# IP5389.net
KiCad netlist of a schematic drawn in Altium Designer
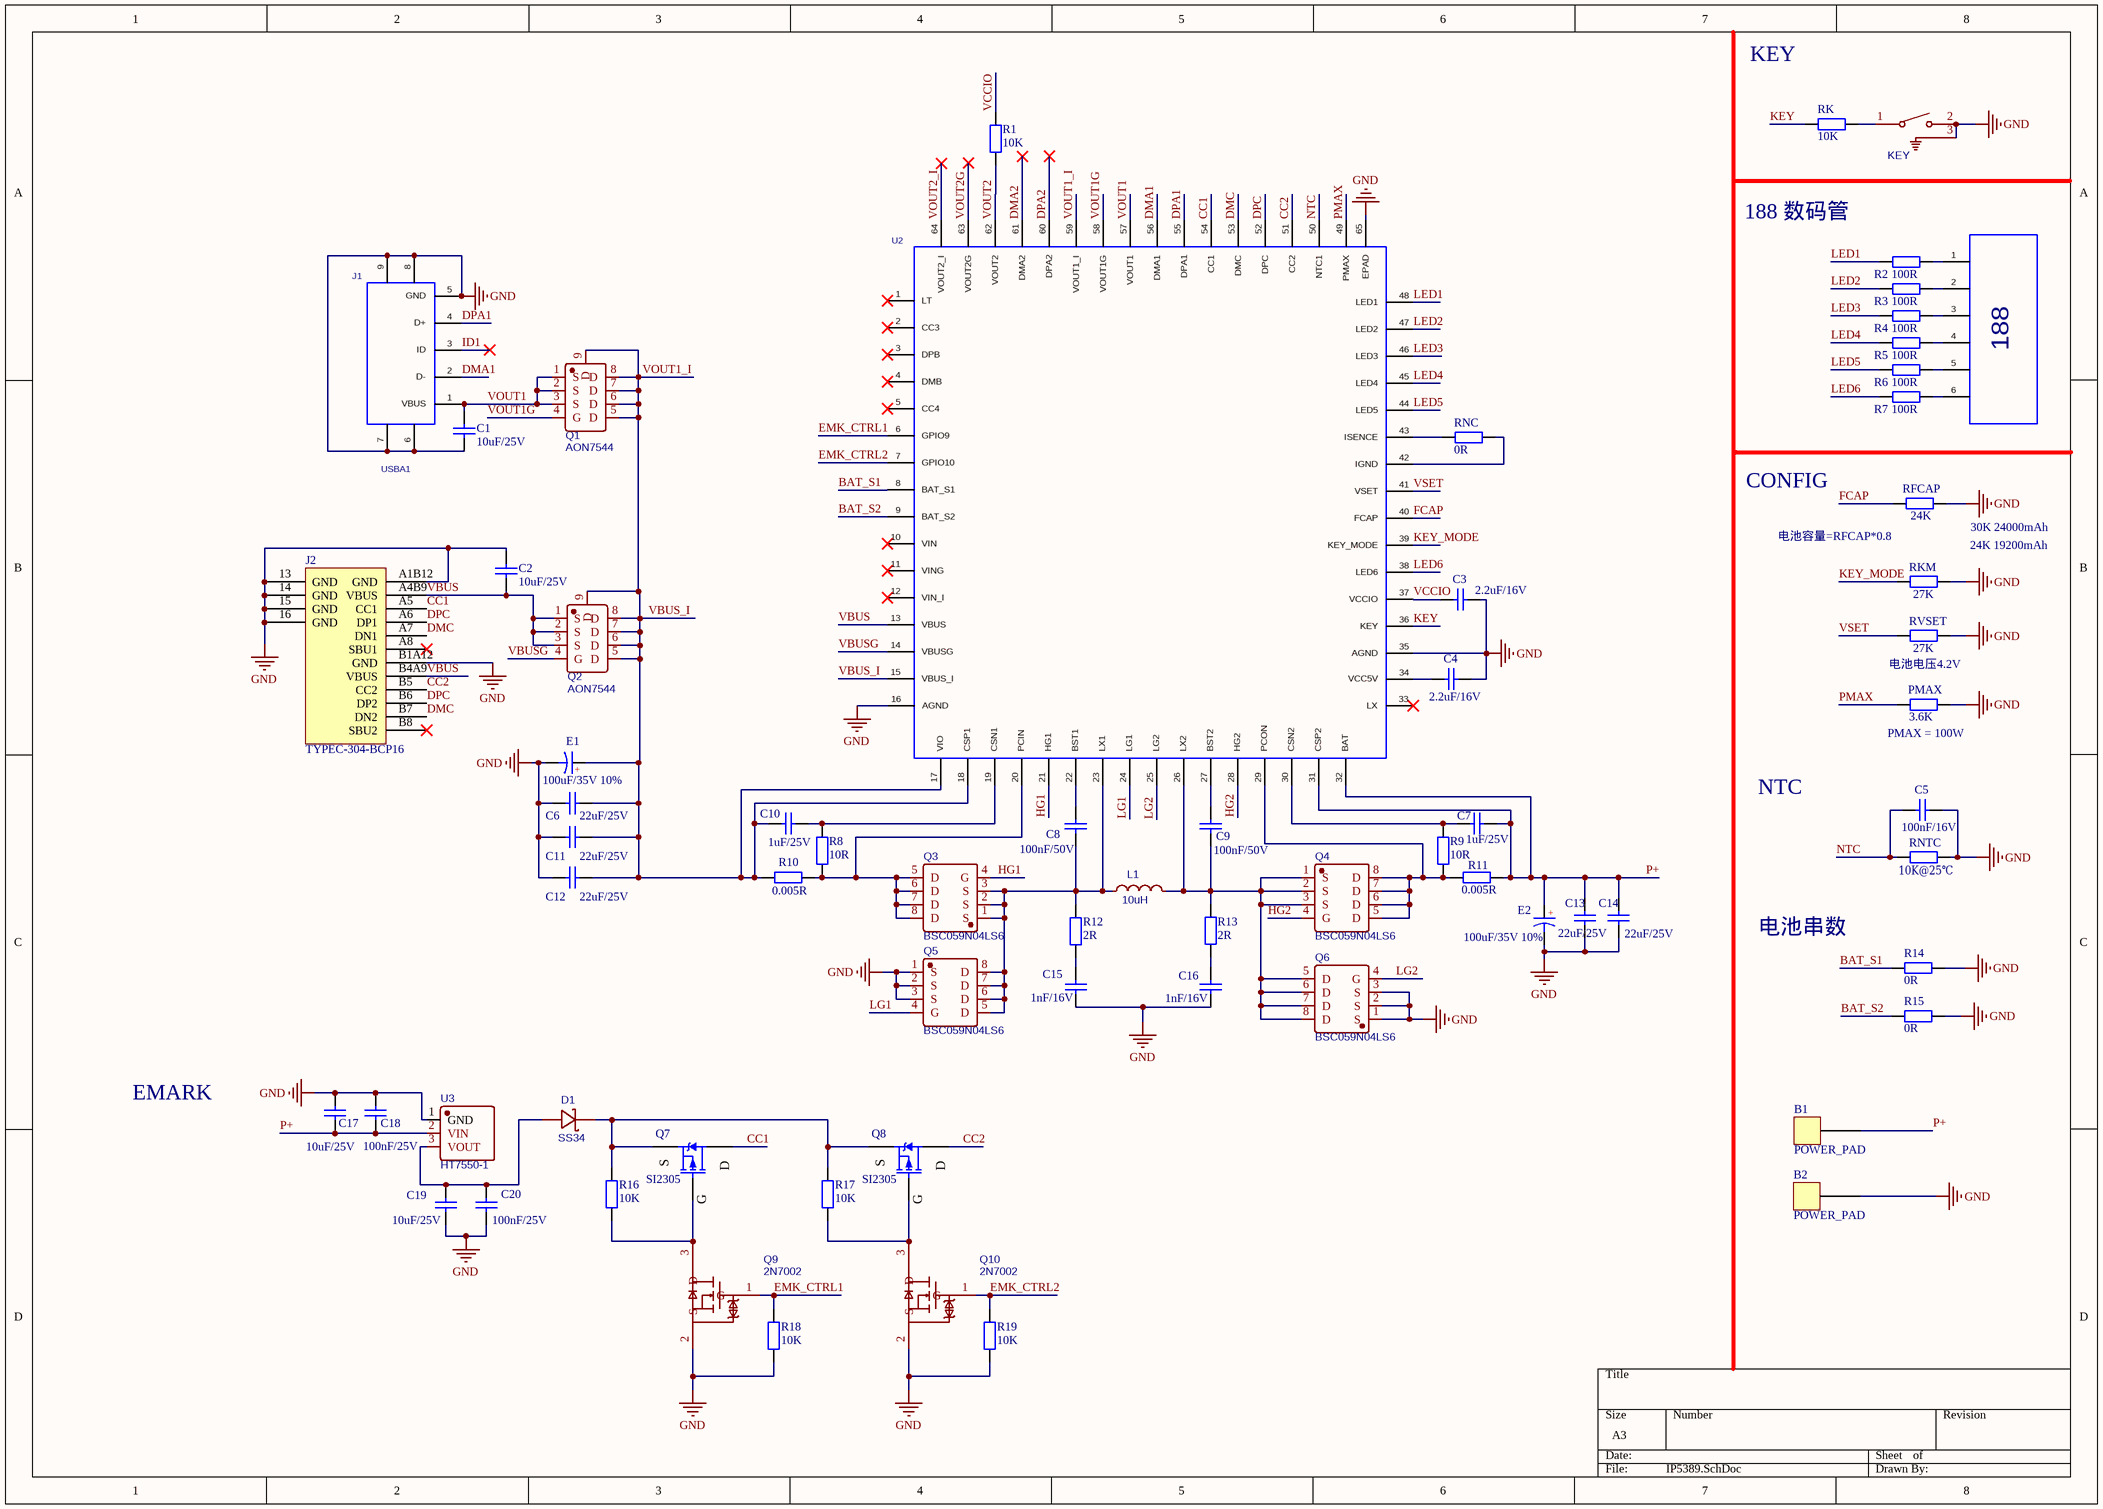
[diagram p0: IP5389.SchDoc]

(export (version "E")
  (design (tool "Eeschema 10.0.6"))
  (components
    (comp (ref "B1")
      (value "POWER_PAD")
      (footprint "POWER_PAD")
      (libsource (lib "IP5389_SCHLIB") (part "POWER_PAD"))
    )
    (comp (ref "B2")
      (value "POWER_PAD")
      (footprint "POWER_PAD")
      (libsource (lib "IP5389_SCHLIB") (part "POWER_PAD"))
    )
    (comp (ref "C1")
      (value "10uF/25V")
      (footprint "C0603_M")
      (description "贴片电容")
      (libsource (lib "0.1 - 电阻-电容-电感-晶振-晶体-磁珠-电位器") (part "C"))
    )
    (comp (ref "C2")
      (value "10uF/25V")
      (footprint "C0603_M")
      (description "贴片电容")
      (libsource (lib "0.1 - 电阻-电容-电感-晶振-晶体-磁珠-电位器") (part "C"))
    )
    (comp (ref "C3")
      (value "2.2uF/16V")
      (footprint "C0603_M")
      (description "贴片电容")
      (libsource (lib "0.1 - 电阻-电容-电感-晶振-晶体-磁珠-电位器") (part "C"))
    )
    (comp (ref "C4")
      (value "2.2uF/16V")
      (footprint "C0603_M")
      (description "贴片电容")
      (libsource (lib "0.1 - 电阻-电容-电感-晶振-晶体-磁珠-电位器") (part "C"))
    )
    (comp (ref "C5")
      (value "100nF/16V")
      (footprint "C0603_M")
      (description "贴片电容")
      (libsource (lib "0.1 - 电阻-电容-电感-晶振-晶体-磁珠-电位器") (part "C"))
    )
    (comp (ref "C6")
      (value "22uF/25V")
      (footprint "C0603_M")
      (description "贴片电容")
      (libsource (lib "0.1 - 电阻-电容-电感-晶振-晶体-磁珠-电位器") (part "C"))
    )
    (comp (ref "C7")
      (value "1uF/25V")
      (footprint "C0603_M")
      (description "贴片电容")
      (libsource (lib "0.1 - 电阻-电容-电感-晶振-晶体-磁珠-电位器") (part "C"))
    )
    (comp (ref "C8")
      (value "100nF/50V")
      (footprint "C0603_M")
      (description "贴片电容")
      (libsource (lib "0.1 - 电阻-电容-电感-晶振-晶体-磁珠-电位器") (part "C"))
    )
    (comp (ref "C9")
      (value "100nF/50V")
      (footprint "C0603_M")
      (description "贴片电容")
      (libsource (lib "0.1 - 电阻-电容-电感-晶振-晶体-磁珠-电位器") (part "C"))
    )
    (comp (ref "C10")
      (value "1uF/25V")
      (footprint "C0603_M")
      (description "贴片电容")
      (libsource (lib "0.1 - 电阻-电容-电感-晶振-晶体-磁珠-电位器") (part "C"))
    )
    (comp (ref "C11")
      (value "22uF/25V")
      (footprint "C0603_M")
      (description "贴片电容")
      (libsource (lib "0.1 - 电阻-电容-电感-晶振-晶体-磁珠-电位器") (part "C"))
    )
    (comp (ref "C12")
      (value "22uF/25V")
      (footprint "C0603_M")
      (description "贴片电容")
      (libsource (lib "0.1 - 电阻-电容-电感-晶振-晶体-磁珠-电位器") (part "C"))
    )
    (comp (ref "C13")
      (value "22uF/25V")
      (footprint "C0603_M")
      (description "贴片电容")
      (libsource (lib "0.1 - 电阻-电容-电感-晶振-晶体-磁珠-电位器") (part "C"))
    )
    (comp (ref "C14")
      (value "22uF/25V")
      (footprint "C0603_M")
      (description "贴片电容")
      (libsource (lib "0.1 - 电阻-电容-电感-晶振-晶体-磁珠-电位器") (part "C"))
    )
    (comp (ref "C15")
      (value "1nF/16V")
      (footprint "C0603_M")
      (description "贴片电容")
      (libsource (lib "0.1 - 电阻-电容-电感-晶振-晶体-磁珠-电位器") (part "C"))
    )
    (comp (ref "C16")
      (value "1nF/16V")
      (footprint "C0603_M")
      (description "贴片电容")
      (libsource (lib "0.1 - 电阻-电容-电感-晶振-晶体-磁珠-电位器") (part "C"))
    )
    (comp (ref "C17")
      (value "10uF/25V")
      (footprint "C0603_M")
      (description "贴片电容")
      (libsource (lib "0.1 - 电阻-电容-电感-晶振-晶体-磁珠-电位器") (part "C"))
    )
    (comp (ref "C18")
      (value "100nF/25V")
      (footprint "C0603_M")
      (description "贴片电容")
      (libsource (lib "0.1 - 电阻-电容-电感-晶振-晶体-磁珠-电位器") (part "C"))
    )
    (comp (ref "C19")
      (value "10uF/25V")
      (footprint "C0603_M")
      (description "贴片电容")
      (libsource (lib "0.1 - 电阻-电容-电感-晶振-晶体-磁珠-电位器") (part "C"))
    )
    (comp (ref "C20")
      (value "100nF/25V")
      (footprint "C0603_M")
      (description "贴片电容")
      (libsource (lib "0.1 - 电阻-电容-电感-晶振-晶体-磁珠-电位器") (part "C"))
    )
    (comp (ref "D1")
      (value "SS34")
      (footprint "SS34-SMA")
      (description "SS34_C408258")
      (fields (field (name "BOM_SUPPLIER PART") "C408258") (field (name "CONTRIBUTOR") "LCSC"))
      (libsource (lib "IP5389_SCHLIB") (part "SS34_C408258"))
    )
    (comp (ref "E1")
      (value "100uF/35V 10%")
      (footprint "CT 2.5*6.3*7 - C")
      (description "直插固态电容")
      (libsource (lib "0.1 - 电阻-电容-电感-晶振-晶体-磁珠-电位器") (part "CS"))
    )
    (comp (ref "E2")
      (value "100uF/35V 10%")
      (footprint "CT 2.5*6.3*7 - C")
      (description "直插固态电容")
      (libsource (lib "0.1 - 电阻-电容-电感-晶振-晶体-磁珠-电位器") (part "CS"))
    )
    (comp (ref "J1")
      (value "USBA1")
      (footprint "USB-A-5P")
      (description "USB母座")
      (libsource (lib "IP5389_SCHLIB") (part "USBA_OPPO_9PIN"))
    )
    (comp (ref "J2")
      (value "TYPEC-304-BCP16")
      (footprint "TYPE-C-16P")
      (description "TYPEC-16P")
      (libsource (lib "IP5389_SCHLIB") (part "TYPEC-304-BCP16"))
    )
    (comp (ref "KEY")
      (value "TC-1109DE-C-G")
      (footprint "SWITCH")
      (description "KEY")
      (fields (field (name "BOM_SUPPLIER PART") "C400325") (field (name "CONTRIBUTOR") "LCSC"))
      (libsource (lib "IP5389_SCHLIB") (part "KEY"))
    )
    (comp (ref "L1")
      (value "10uH")
      (footprint "10uH")
      (fields
        (field (name "BOM_SUPPLIER PART") "C242228")
        (field (name "BOM_MANUFACTURER PART") "SLO1365S100MTT")
        (field (name "CONTRIBUTOR") "LCSC")
      )
      (libsource (lib "IP5389_SCHLIB") (part "10uH"))
    )
    (comp (ref "PMAX")
      (value "3.6K")
      (footprint "R0603_M")
      (description "贴片电阻")
      (libsource (lib "0.1 - 电阻-电容-电感-晶振-晶体-磁珠-电位器") (part "R"))
    )
    (comp (ref "Q1")
      (value "AON7544")
      (footprint "DFN-8_L3.0-W3.0-P0.65-BL")
      (description "NMOS 30V 30A")
      (fields (field (name "BOM_SUPPLIER PART") "C315567") (field (name "CONTRIBUTOR") "LCSC"))
      (libsource (lib "IP5389_SCHLIB") (part "AON7544"))
    )
    (comp (ref "Q2")
      (value "AON7544")
      (footprint "DFN-8_L3.0-W3.0-P0.65-BL")
      (description "NMOS 30V 30A")
      (fields (field (name "BOM_SUPPLIER PART") "C315567") (field (name "CONTRIBUTOR") "LCSC"))
      (libsource (lib "IP5389_SCHLIB") (part "AON7544"))
    )
    (comp (ref "Q3")
      (value "BSC059N04LS6")
      (footprint "PG-TDSON-8_L5.0-W6.0-P1.27-BL-EP")
      (fields (field (name "BOM_SUPPLIER PART") "C534356") (field (name "CONTRIBUTOR") "LCSC"))
      (libsource (lib "IP5389_SCHLIB") (part "BSC059N04LS6"))
    )
    (comp (ref "Q4")
      (value "BSC059N04LS6")
      (footprint "PG-TDSON-8_L5.0-W6.0-P1.27-BL-EP")
      (fields (field (name "BOM_SUPPLIER PART") "C534356") (field (name "CONTRIBUTOR") "LCSC"))
      (libsource (lib "IP5389_SCHLIB") (part "BSC059N04LS6"))
    )
    (comp (ref "Q5")
      (value "BSC059N04LS6")
      (footprint "PG-TDSON-8_L5.0-W6.0-P1.27-BL-EP")
      (fields (field (name "BOM_SUPPLIER PART") "C534356") (field (name "CONTRIBUTOR") "LCSC"))
      (libsource (lib "IP5389_SCHLIB") (part "BSC059N04LS6"))
    )
    (comp (ref "Q6")
      (value "BSC059N04LS6")
      (footprint "PG-TDSON-8_L5.0-W6.0-P1.27-BL-EP")
      (fields (field (name "BOM_SUPPLIER PART") "C534356") (field (name "CONTRIBUTOR") "LCSC"))
      (libsource (lib "IP5389_SCHLIB") (part "BSC059N04LS6"))
    )
    (comp (ref "Q7")
      (value "SI2305")
      (footprint "SOT23-3M")
      (description "P沟道 20V/2.8A")
      (libsource (lib "0.4 - 三极管-场效应管-可控硅") (part "SI2305"))
    )
    (comp (ref "Q8")
      (value "SI2305")
      (footprint "SOT23-3M")
      (description "P沟道 20V/2.8A")
      (libsource (lib "0.4 - 三极管-场效应管-可控硅") (part "SI2305"))
    )
    (comp (ref "Q9")
      (value "2N7002")
      (footprint "SOT-23-3_L2.9-W1.3-P1.90-LS2.4-BR")
      (description "2N7002_C916396")
      (fields (field (name "BOM_SUPPLIER PART") "C916396") (field (name "CONTRIBUTOR") "LCSC"))
      (libsource (lib "IP5389_SCHLIB") (part "2N7002_C916396"))
    )
    (comp (ref "Q10")
      (value "2N7002")
      (footprint "SOT-23-3_L2.9-W1.3-P1.90-LS2.4-BR")
      (description "2N7002_C916396")
      (fields (field (name "BOM_SUPPLIER PART") "C916396") (field (name "CONTRIBUTOR") "LCSC"))
      (libsource (lib "IP5389_SCHLIB") (part "2N7002_C916396"))
    )
    (comp (ref "R1")
      (value "10K")
      (footprint "R0603_M")
      (description "贴片电阻")
      (libsource (lib "0.1 - 电阻-电容-电感-晶振-晶体-磁珠-电位器") (part "R"))
    )
    (comp (ref "R2")
      (value "100R")
      (footprint "R0603_M")
      (description "贴片电阻")
      (libsource (lib "0.1 - 电阻-电容-电感-晶振-晶体-磁珠-电位器") (part "R"))
    )
    (comp (ref "R3")
      (value "100R")
      (footprint "R0603_M")
      (description "贴片电阻")
      (libsource (lib "0.1 - 电阻-电容-电感-晶振-晶体-磁珠-电位器") (part "R"))
    )
    (comp (ref "R4")
      (value "100R")
      (footprint "R0603_M")
      (description "贴片电阻")
      (libsource (lib "0.1 - 电阻-电容-电感-晶振-晶体-磁珠-电位器") (part "R"))
    )
    (comp (ref "R5")
      (value "100R")
      (footprint "R0603_M")
      (description "贴片电阻")
      (libsource (lib "0.1 - 电阻-电容-电感-晶振-晶体-磁珠-电位器") (part "R"))
    )
    (comp (ref "R6")
      (value "100R")
      (footprint "R0603_M")
      (description "贴片电阻")
      (libsource (lib "0.1 - 电阻-电容-电感-晶振-晶体-磁珠-电位器") (part "R"))
    )
    (comp (ref "R7")
      (value "100R")
      (footprint "R0603_M")
      (description "贴片电阻")
      (libsource (lib "0.1 - 电阻-电容-电感-晶振-晶体-磁珠-电位器") (part "R"))
    )
    (comp (ref "R8")
      (value "10R")
      (footprint "R0603_M")
      (description "贴片电阻")
      (libsource (lib "0.1 - 电阻-电容-电感-晶振-晶体-磁珠-电位器") (part "R"))
    )
    (comp (ref "R9")
      (value "10R")
      (footprint "R0603_M")
      (description "贴片电阻")
      (libsource (lib "0.1 - 电阻-电容-电感-晶振-晶体-磁珠-电位器") (part "R"))
    )
    (comp (ref "R10")
      (value "0.005R")
      (footprint "R1206_L")
      (description "贴片电阻")
      (libsource (lib "0.1 - 电阻-电容-电感-晶振-晶体-磁珠-电位器") (part "R"))
    )
    (comp (ref "R11")
      (value "0.005R")
      (footprint "R1206_L")
      (description "贴片电阻")
      (libsource (lib "0.1 - 电阻-电容-电感-晶振-晶体-磁珠-电位器") (part "R"))
    )
    (comp (ref "R12")
      (value "2R")
      (footprint "R0603_M")
      (description "贴片电阻")
      (libsource (lib "0.1 - 电阻-电容-电感-晶振-晶体-磁珠-电位器") (part "R"))
    )
    (comp (ref "R13")
      (value "2R")
      (footprint "R0603_M")
      (description "贴片电阻")
      (libsource (lib "0.1 - 电阻-电容-电感-晶振-晶体-磁珠-电位器") (part "R"))
    )
    (comp (ref "R14")
      (value "0R")
      (footprint "R0603_M")
      (description "贴片电阻")
      (libsource (lib "0.1 - 电阻-电容-电感-晶振-晶体-磁珠-电位器") (part "R"))
    )
    (comp (ref "R15")
      (value "0R")
      (footprint "R0603_M")
      (description "贴片电阻")
      (libsource (lib "0.1 - 电阻-电容-电感-晶振-晶体-磁珠-电位器") (part "R"))
    )
    (comp (ref "R16")
      (value "10K")
      (footprint "R0603_M")
      (description "贴片电阻")
      (libsource (lib "0.1 - 电阻-电容-电感-晶振-晶体-磁珠-电位器") (part "R"))
    )
    (comp (ref "R17")
      (value "10K")
      (footprint "R0603_M")
      (description "贴片电阻")
      (libsource (lib "0.1 - 电阻-电容-电感-晶振-晶体-磁珠-电位器") (part "R"))
    )
    (comp (ref "R18")
      (value "10K")
      (footprint "R0603_M")
      (description "贴片电阻")
      (libsource (lib "0.1 - 电阻-电容-电感-晶振-晶体-磁珠-电位器") (part "R"))
    )
    (comp (ref "R19")
      (value "10K")
      (footprint "R0603_M")
      (description "贴片电阻")
      (libsource (lib "0.1 - 电阻-电容-电感-晶振-晶体-磁珠-电位器") (part "R"))
    )
    (comp (ref "RFCAP")
      (value "24K")
      (footprint "R0603_M")
      (description "贴片电阻")
      (libsource (lib "0.1 - 电阻-电容-电感-晶振-晶体-磁珠-电位器") (part "R"))
    )
    (comp (ref "RK")
      (value "10K")
      (footprint "R0603_M")
      (description "贴片电阻")
      (libsource (lib "0.1 - 电阻-电容-电感-晶振-晶体-磁珠-电位器") (part "R"))
    )
    (comp (ref "RKM")
      (value "27K")
      (footprint "R0603_M")
      (description "贴片电阻")
      (libsource (lib "0.1 - 电阻-电容-电感-晶振-晶体-磁珠-电位器") (part "R"))
    )
    (comp (ref "RNC")
      (value "0R")
      (footprint "R0603_M")
      (description "贴片电阻")
      (libsource (lib "0.1 - 电阻-电容-电感-晶振-晶体-磁珠-电位器") (part "R"))
    )
    (comp (ref "RNTC")
      (value "10K@25℃")
      (footprint "R0603_M")
      (description "10K@25℃ B=3380")
      (libsource (lib "0.1 - 电阻-电容-电感-晶振-晶体-磁珠-电位器") (part "R"))
    )
    (comp (ref "RVSET")
      (value "27K")
      (footprint "R0603_M")
      (description "贴片电阻")
      (libsource (lib "0.1 - 电阻-电容-电感-晶振-晶体-磁珠-电位器") (part "R"))
    )
    (comp (ref "U1")
      (value "SMG_6PIN")
      (footprint "188SMG")
      (description "188数码管")
      (libsource (lib "IP5389_SCHLIB") (part "SMG_6PIN"))
    )
    (comp (ref "U2")
      (value "IP5389")
      (footprint "IP5389")
      (description "IP5389 QFN64")
      (libsource (lib "IP5389_SCHLIB") (part "IP5389"))
    )
    (comp (ref "U3")
      (value "HT7550-1")
      (footprint "SOT89_N")
      (description "5V TinyPower LDO")
      (fields (field (name "BOM_SUPPLIER PART") "C347189") (field (name "CONTRIBUTOR") "LCSC"))
      (libsource (lib "IP5389_SCHLIB") (part "HT7550-1_C347189"))
    )
  )
  (nets
    (net (code "1") (name "/BAT_S1") (class "Default")
      (node (ref "R14") (pin "1") (pinfunction "1_1") (pintype "passive"))
      (node (ref "U2") (pin "8") (pinfunction "BAT_S1_8") (pintype "passive"))
    )
    (net (code "2") (name "/BAT_S2") (class "Default")
      (node (ref "R15") (pin "1") (pinfunction "1_1") (pintype "passive"))
      (node (ref "U2") (pin "9") (pinfunction "BAT_S2_9") (pintype "passive"))
    )
    (net (code "3") (name "/CC1") (class "Default")
      (node (ref "J2") (pin "A5") (pinfunction "CC1_A5") (pintype "passive"))
      (node (ref "Q7") (pin "3") (pinfunction "D_3") (pintype "passive"))
      (node (ref "U2") (pin "54") (pinfunction "CC1_54") (pintype "passive"))
    )
    (net (code "4") (name "/CC2") (class "Default")
      (node (ref "J2") (pin "B5") (pinfunction "CC2_B5") (pintype "passive"))
      (node (ref "Q8") (pin "3") (pinfunction "D_3") (pintype "passive"))
      (node (ref "U2") (pin "51") (pinfunction "CC2_51") (pintype "passive"))
    )
    (net (code "5") (name "/DMA1") (class "Default")
      (node (ref "J1") (pin "2") (pinfunction "D-_2") (pintype "passive"))
      (node (ref "U2") (pin "56") (pinfunction "DMA1_56") (pintype "passive"))
    )
    (net (code "6") (name "/DMA2") (class "Default")
      (node (ref "U2") (pin "61") (pinfunction "DMA2_61") (pintype "passive+no_connect"))
    )
    (net (code "7") (name "/DMC") (class "Default")
      (node (ref "J2") (pin "A7") (pinfunction "DN1_A7") (pintype "passive"))
      (node (ref "J2") (pin "B7") (pinfunction "DN2_B7") (pintype "passive"))
      (node (ref "U2") (pin "53") (pinfunction "DMC_53") (pintype "passive"))
    )
    (net (code "8") (name "/DPA1") (class "Default")
      (node (ref "J1") (pin "4") (pinfunction "D+_4") (pintype "passive"))
      (node (ref "U2") (pin "55") (pinfunction "DPA1_55") (pintype "passive"))
    )
    (net (code "9") (name "/DPA2") (class "Default")
      (node (ref "U2") (pin "60") (pinfunction "DPA2_60") (pintype "passive+no_connect"))
    )
    (net (code "10") (name "/DPC") (class "Default")
      (node (ref "J2") (pin "A6") (pinfunction "DP1_A6") (pintype "passive"))
      (node (ref "J2") (pin "B6") (pinfunction "DP2_B6") (pintype "passive"))
      (node (ref "U2") (pin "52") (pinfunction "DPC_52") (pintype "passive"))
    )
    (net (code "11") (name "/EMK_CTRL1") (class "Default")
      (node (ref "Q9") (pin "1") (pinfunction "G_1") (pintype "passive"))
      (node (ref "R18") (pin "2") (pinfunction "2_2") (pintype "passive"))
      (node (ref "U2") (pin "6") (pinfunction "GPIO9_6") (pintype "passive"))
    )
    (net (code "12") (name "/EMK_CTRL2") (class "Default")
      (node (ref "Q10") (pin "1") (pinfunction "G_1") (pintype "passive"))
      (node (ref "R19") (pin "2") (pinfunction "2_2") (pintype "passive"))
      (node (ref "U2") (pin "7") (pinfunction "GPIO10_7") (pintype "passive"))
    )
    (net (code "13") (name "/FCAP") (class "Default")
      (node (ref "RFCAP") (pin "1") (pinfunction "1_1") (pintype "passive"))
      (node (ref "U2") (pin "40") (pinfunction "FCAP_40") (pintype "passive"))
    )
    (net (code "14") (name "/HG1") (class "Default")
      (node (ref "Q3") (pin "4") (pinfunction "G_4") (pintype "passive"))
      (node (ref "U2") (pin "21") (pinfunction "HG1_21") (pintype "passive"))
    )
    (net (code "15") (name "/HG2") (class "Default")
      (node (ref "Q4") (pin "4") (pinfunction "G_4") (pintype "passive"))
      (node (ref "U2") (pin "28") (pinfunction "HG2_28") (pintype "passive"))
    )
    (net (code "16") (name "/ID1") (class "Default")
      (node (ref "J1") (pin "3") (pinfunction "ID_3") (pintype "passive+no_connect"))
    )
    (net (code "17") (name "/KEY") (class "Default")
      (node (ref "RK") (pin "1") (pinfunction "1_1") (pintype "passive"))
      (node (ref "U2") (pin "36") (pinfunction "KEY_36") (pintype "passive"))
    )
    (net (code "18") (name "/KEY_MODE") (class "Default")
      (node (ref "RKM") (pin "1") (pinfunction "1_1") (pintype "passive"))
      (node (ref "U2") (pin "39") (pinfunction "KEY_MODE_39") (pintype "passive"))
    )
    (net (code "19") (name "/LED1") (class "Default")
      (node (ref "R2") (pin "1") (pinfunction "1_1") (pintype "passive"))
      (node (ref "U2") (pin "48") (pinfunction "LED1_48") (pintype "passive"))
    )
    (net (code "20") (name "/LED2") (class "Default")
      (node (ref "R3") (pin "1") (pinfunction "1_1") (pintype "passive"))
      (node (ref "U2") (pin "47") (pinfunction "LED2_47") (pintype "passive"))
    )
    (net (code "21") (name "/LED3") (class "Default")
      (node (ref "R4") (pin "1") (pinfunction "1_1") (pintype "passive"))
      (node (ref "U2") (pin "46") (pinfunction "LED3_46") (pintype "passive"))
    )
    (net (code "22") (name "/LED4") (class "Default")
      (node (ref "R5") (pin "1") (pinfunction "1_1") (pintype "passive"))
      (node (ref "U2") (pin "45") (pinfunction "LED4_45") (pintype "passive"))
    )
    (net (code "23") (name "/LED5") (class "Default")
      (node (ref "R6") (pin "1") (pinfunction "1_1") (pintype "passive"))
      (node (ref "U2") (pin "44") (pinfunction "LED5_44") (pintype "passive"))
    )
    (net (code "24") (name "/LED6") (class "Default")
      (node (ref "R7") (pin "1") (pinfunction "1_1") (pintype "passive"))
      (node (ref "U2") (pin "38") (pinfunction "LED6_38") (pintype "passive"))
    )
    (net (code "25") (name "/LG1") (class "Default")
      (node (ref "Q5") (pin "4") (pinfunction "G_4") (pintype "passive"))
      (node (ref "U2") (pin "24") (pinfunction "LG1_24") (pintype "passive"))
    )
    (net (code "26") (name "/LG2") (class "Default")
      (node (ref "Q6") (pin "4") (pinfunction "G_4") (pintype "passive"))
      (node (ref "U2") (pin "25") (pinfunction "LG2_25") (pintype "passive"))
    )
    (net (code "27") (name "/NTC") (class "Default")
      (node (ref "C5") (pin "1") (pinfunction "1_1") (pintype "passive"))
      (node (ref "RNTC") (pin "1") (pinfunction "1_1") (pintype "passive"))
      (node (ref "U2") (pin "50") (pinfunction "NTC1_50") (pintype "passive"))
    )
    (net (code "28") (name "/P+") (class "Default")
      (node (ref "B1") (pin "1") (pinfunction "1_1") (pintype "passive"))
      (node (ref "C13") (pin "2") (pinfunction "2_2") (pintype "passive"))
      (node (ref "C14") (pin "2") (pinfunction "2_2") (pintype "passive"))
      (node (ref "C17") (pin "1") (pinfunction "1_1") (pintype "passive"))
      (node (ref "C18") (pin "1") (pinfunction "1_1") (pintype "passive"))
      (node (ref "C7") (pin "2") (pinfunction "2_2") (pintype "passive"))
      (node (ref "E2") (pin "1") (pinfunction "1_1") (pintype "passive"))
      (node (ref "R11") (pin "2") (pinfunction "2_2") (pintype "passive"))
      (node (ref "U2") (pin "31") (pinfunction "CSP2_31") (pintype "passive"))
      (node (ref "U2") (pin "32") (pinfunction "BAT_32") (pintype "passive"))
      (node (ref "U3") (pin "2") (pinfunction "VIN_2") (pintype "passive"))
    )
    (net (code "29") (name "/PMAX") (class "Default")
      (node (ref "PMAX") (pin "1") (pinfunction "1_1") (pintype "passive"))
      (node (ref "U2") (pin "49") (pinfunction "PMAX_49") (pintype "passive"))
    )
    (net (code "30") (name "/VBUS") (class "Default")
      (node (ref "C2") (pin "1") (pinfunction "1_1") (pintype "passive"))
      (node (ref "J2") (pin "A4B9") (pinfunction "VBUS_A4B9") (pintype "passive"))
      (node (ref "J2") (pin "B4A9") (pinfunction "VBUS_B4A9") (pintype "passive"))
      (node (ref "Q2") (pin "1") (pinfunction "S_1") (pintype "passive"))
      (node (ref "Q2") (pin "2") (pinfunction "S_2") (pintype "passive"))
      (node (ref "Q2") (pin "3") (pinfunction "S_3") (pintype "passive"))
      (node (ref "U2") (pin "13") (pinfunction "VBUS_13") (pintype "passive"))
    )
    (net (code "31") (name "/VBUSG") (class "Default")
      (node (ref "Q2") (pin "4") (pinfunction "G_4") (pintype "passive"))
      (node (ref "U2") (pin "14") (pinfunction "VBUSG_14") (pintype "passive"))
    )
    (net (code "32") (name "/VBUS_I") (class "Default")
      (node (ref "C10") (pin "1") (pinfunction "1_1") (pintype "passive"))
      (node (ref "C11") (pin "2") (pinfunction "2_2") (pintype "passive"))
      (node (ref "C12") (pin "2") (pinfunction "2_2") (pintype "passive"))
      (node (ref "C6") (pin "2") (pinfunction "2_2") (pintype "passive"))
      (node (ref "E1") (pin "1") (pinfunction "1_1") (pintype "passive"))
      (node (ref "Q1") (pin "5") (pinfunction "D_5") (pintype "passive"))
      (node (ref "Q1") (pin "6") (pinfunction "D_6") (pintype "passive"))
      (node (ref "Q1") (pin "7") (pinfunction "D_7") (pintype "passive"))
      (node (ref "Q1") (pin "8") (pinfunction "D_8") (pintype "passive"))
      (node (ref "Q1") (pin "9") (pinfunction "D_9") (pintype "passive"))
      (node (ref "Q2") (pin "5") (pinfunction "D_5") (pintype "passive"))
      (node (ref "Q2") (pin "6") (pinfunction "D_6") (pintype "passive"))
      (node (ref "Q2") (pin "7") (pinfunction "D_7") (pintype "passive"))
      (node (ref "Q2") (pin "8") (pinfunction "D_8") (pintype "passive"))
      (node (ref "Q2") (pin "9") (pinfunction "D_9") (pintype "passive"))
      (node (ref "R10") (pin "1") (pinfunction "1_1") (pintype "passive"))
      (node (ref "U2") (pin "15") (pinfunction "VBUS_I_15") (pintype "passive"))
      (node (ref "U2") (pin "17") (pinfunction "VIO_17") (pintype "passive"))
      (node (ref "U2") (pin "18") (pinfunction "CSP1_18") (pintype "passive"))
      (node (ref "U2") (pin "59") (pinfunction "VOUT1_I_59") (pintype "passive"))
    )
    (net (code "33") (name "/VCCIO") (class "Default")
      (node (ref "C3") (pin "1") (pinfunction "1_1") (pintype "passive"))
      (node (ref "R1") (pin "2") (pinfunction "2_2") (pintype "passive"))
      (node (ref "U2") (pin "37") (pinfunction "VCCIO_37") (pintype "passive"))
    )
    (net (code "34") (name "/VOUT1") (class "Default")
      (node (ref "C1") (pin "2") (pinfunction "2_2") (pintype "passive"))
      (node (ref "J1") (pin "1") (pinfunction "VBUS_1") (pintype "passive"))
      (node (ref "Q1") (pin "1") (pinfunction "S_1") (pintype "passive"))
      (node (ref "Q1") (pin "2") (pinfunction "S_2") (pintype "passive"))
      (node (ref "Q1") (pin "3") (pinfunction "S_3") (pintype "passive"))
      (node (ref "U2") (pin "57") (pinfunction "VOUT1_57") (pintype "passive"))
    )
    (net (code "35") (name "/VOUT1G") (class "Default")
      (node (ref "Q1") (pin "4") (pinfunction "G_4") (pintype "passive"))
      (node (ref "U2") (pin "58") (pinfunction "VOUT1G_58") (pintype "passive"))
    )
    (net (code "36") (name "/VOUT2") (class "Default")
      (node (ref "R1") (pin "1") (pinfunction "1_1") (pintype "passive"))
      (node (ref "U2") (pin "62") (pinfunction "VOUT2_62") (pintype "passive"))
    )
    (net (code "37") (name "/VOUT2G") (class "Default")
      (node (ref "U2") (pin "63") (pinfunction "VOUT2G_63") (pintype "passive+no_connect"))
    )
    (net (code "38") (name "/VOUT2_I") (class "Default")
      (node (ref "U2") (pin "64") (pinfunction "VOUT2_I_64") (pintype "passive+no_connect"))
    )
    (net (code "39") (name "/VSET") (class "Default")
      (node (ref "RVSET") (pin "1") (pinfunction "1_1") (pintype "passive"))
      (node (ref "U2") (pin "41") (pinfunction "VSET_41") (pintype "passive"))
    )
    (net (code "40") (name "GND") (class "Default")
      (node (ref "B2") (pin "1") (pinfunction "1_1") (pintype "passive"))
      (node (ref "C1") (pin "1") (pinfunction "1_1") (pintype "passive"))
      (node (ref "C11") (pin "1") (pinfunction "1_1") (pintype "passive"))
      (node (ref "C12") (pin "1") (pinfunction "1_1") (pintype "passive"))
      (node (ref "C13") (pin "1") (pinfunction "1_1") (pintype "passive"))
      (node (ref "C14") (pin "1") (pinfunction "1_1") (pintype "passive"))
      (node (ref "C15") (pin "1") (pinfunction "1_1") (pintype "passive"))
      (node (ref "C16") (pin "1") (pinfunction "1_1") (pintype "passive"))
      (node (ref "C17") (pin "2") (pinfunction "2_2") (pintype "passive"))
      (node (ref "C18") (pin "2") (pinfunction "2_2") (pintype "passive"))
      (node (ref "C19") (pin "1") (pinfunction "1_1") (pintype "passive"))
      (node (ref "C2") (pin "2") (pinfunction "2_2") (pintype "passive"))
      (node (ref "C20") (pin "1") (pinfunction "1_1") (pintype "passive"))
      (node (ref "C3") (pin "2") (pinfunction "2_2") (pintype "passive"))
      (node (ref "C4") (pin "2") (pinfunction "2_2") (pintype "passive"))
      (node (ref "C5") (pin "2") (pinfunction "2_2") (pintype "passive"))
      (node (ref "C6") (pin "1") (pinfunction "1_1") (pintype "passive"))
      (node (ref "E1") (pin "2") (pinfunction "2_2") (pintype "passive"))
      (node (ref "E2") (pin "2") (pinfunction "2_2") (pintype "passive"))
      (node (ref "J1") (pin "5") (pinfunction "GND_5") (pintype "passive"))
      (node (ref "J1") (pin "6") (pinfunction "6_6") (pintype "passive"))
      (node (ref "J1") (pin "7") (pinfunction "7_7") (pintype "passive"))
      (node (ref "J1") (pin "8") (pinfunction "8_8") (pintype "passive"))
      (node (ref "J1") (pin "9") (pinfunction "9_9") (pintype "passive"))
      (node (ref "J2") (pin "13") (pinfunction "GND_13") (pintype "passive"))
      (node (ref "J2") (pin "14") (pinfunction "GND_14") (pintype "passive"))
      (node (ref "J2") (pin "15") (pinfunction "GND_15") (pintype "passive"))
      (node (ref "J2") (pin "16") (pinfunction "GND_16") (pintype "passive"))
      (node (ref "J2") (pin "A1B12") (pinfunction "GND_A1B12") (pintype "passive"))
      (node (ref "J2") (pin "B1A12") (pinfunction "GND_B1A12") (pintype "passive"))
      (node (ref "KEY") (pin "2") (pinfunction "2_2") (pintype "passive"))
      (node (ref "KEY") (pin "3") (pinfunction "3_3") (pintype "passive"))
      (node (ref "PMAX") (pin "2") (pinfunction "2_2") (pintype "passive"))
      (node (ref "Q10") (pin "2") (pinfunction "S_2") (pintype "passive"))
      (node (ref "Q5") (pin "1") (pinfunction "S_1") (pintype "passive"))
      (node (ref "Q5") (pin "2") (pinfunction "S_2") (pintype "passive"))
      (node (ref "Q5") (pin "3") (pinfunction "S_3") (pintype "passive"))
      (node (ref "Q6") (pin "1") (pinfunction "S_1") (pintype "passive"))
      (node (ref "Q6") (pin "2") (pinfunction "S_2") (pintype "passive"))
      (node (ref "Q6") (pin "3") (pinfunction "S_3") (pintype "passive"))
      (node (ref "Q9") (pin "2") (pinfunction "S_2") (pintype "passive"))
      (node (ref "R14") (pin "2") (pinfunction "2_2") (pintype "passive"))
      (node (ref "R15") (pin "2") (pinfunction "2_2") (pintype "passive"))
      (node (ref "R18") (pin "1") (pinfunction "1_1") (pintype "passive"))
      (node (ref "R19") (pin "1") (pinfunction "1_1") (pintype "passive"))
      (node (ref "RFCAP") (pin "2") (pinfunction "2_2") (pintype "passive"))
      (node (ref "RKM") (pin "2") (pinfunction "2_2") (pintype "passive"))
      (node (ref "RNTC") (pin "2") (pinfunction "2_2") (pintype "passive"))
      (node (ref "RVSET") (pin "2") (pinfunction "2_2") (pintype "passive"))
      (node (ref "U2") (pin "16") (pinfunction "AGND_16") (pintype "passive"))
      (node (ref "U2") (pin "35") (pinfunction "AGND_35") (pintype "passive"))
      (node (ref "U2") (pin "65") (pinfunction "EPAD_65") (pintype "passive"))
      (node (ref "U3") (pin "1") (pinfunction "GND_1") (pintype "passive"))
    )
    (net (code "41") (name "Net-(C15-Pad2)") (class "Default")
      (node (ref "C15") (pin "2") (pinfunction "2_2") (pintype "passive"))
      (node (ref "R12") (pin "1") (pinfunction "1_1") (pintype "passive"))
    )
    (net (code "42") (name "Net-(C16-Pad2)") (class "Default")
      (node (ref "C16") (pin "2") (pinfunction "2_2") (pintype "passive"))
      (node (ref "R13") (pin "1") (pinfunction "1_1") (pintype "passive"))
    )
    (net (code "43") (name "Net-(D1-A)") (class "Default")
      (node (ref "C19") (pin "2") (pinfunction "2_2") (pintype "passive"))
      (node (ref "C20") (pin "2") (pinfunction "2_2") (pintype "passive"))
      (node (ref "D1") (pin "2") (pinfunction "A_2") (pintype "passive"))
      (node (ref "U3") (pin "3") (pinfunction "VOUT_3") (pintype "passive"))
    )
    (net (code "44") (name "Net-(D1-C)") (class "Default")
      (node (ref "D1") (pin "1") (pinfunction "C_1") (pintype "passive"))
      (node (ref "Q7") (pin "2") (pinfunction "S_2") (pintype "passive"))
      (node (ref "Q8") (pin "2") (pinfunction "S_2") (pintype "passive"))
      (node (ref "R16") (pin "2") (pinfunction "2_2") (pintype "passive"))
      (node (ref "R17") (pin "2") (pinfunction "2_2") (pintype "passive"))
    )
    (net (code "45") (name "Net-(KEY-Pad1)") (class "Default")
      (node (ref "KEY") (pin "1") (pinfunction "1_1") (pintype "passive"))
      (node (ref "RK") (pin "2") (pinfunction "2_2") (pintype "passive"))
    )
    (net (code "46") (name "Net-(Q7-G)") (class "Default")
      (node (ref "Q7") (pin "1") (pinfunction "G_1") (pintype "passive"))
      (node (ref "Q9") (pin "3") (pinfunction "D_3") (pintype "passive"))
      (node (ref "R16") (pin "1") (pinfunction "1_1") (pintype "passive"))
    )
    (net (code "47") (name "Net-(Q10-D)") (class "Default")
      (node (ref "Q10") (pin "3") (pinfunction "D_3") (pintype "passive"))
      (node (ref "Q8") (pin "1") (pinfunction "G_1") (pintype "passive"))
      (node (ref "R17") (pin "1") (pinfunction "1_1") (pintype "passive"))
    )
    (net (code "48") (name "Net-(R2-Pad2)") (class "Default")
      (node (ref "R2") (pin "2") (pinfunction "2_2") (pintype "passive"))
      (node (ref "U1") (pin "1") (pinfunction "1_1") (pintype "passive"))
    )
    (net (code "49") (name "Net-(R3-Pad2)") (class "Default")
      (node (ref "R3") (pin "2") (pinfunction "2_2") (pintype "passive"))
      (node (ref "U1") (pin "2") (pinfunction "2_2") (pintype "passive"))
    )
    (net (code "50") (name "Net-(R4-Pad2)") (class "Default")
      (node (ref "R4") (pin "2") (pinfunction "2_2") (pintype "passive"))
      (node (ref "U1") (pin "3") (pinfunction "3_3") (pintype "passive"))
    )
    (net (code "51") (name "Net-(R5-Pad2)") (class "Default")
      (node (ref "R5") (pin "2") (pinfunction "2_2") (pintype "passive"))
      (node (ref "U1") (pin "4") (pinfunction "4_4") (pintype "passive"))
    )
    (net (code "52") (name "Net-(R6-Pad2)") (class "Default")
      (node (ref "R6") (pin "2") (pinfunction "2_2") (pintype "passive"))
      (node (ref "U1") (pin "5") (pinfunction "5_5") (pintype "passive"))
    )
    (net (code "53") (name "Net-(R7-Pad2)") (class "Default")
      (node (ref "R7") (pin "2") (pinfunction "2_2") (pintype "passive"))
      (node (ref "U1") (pin "6") (pinfunction "6_6") (pintype "passive"))
    )
    (net (code "54") (name "Net-(U2-BST1)") (class "Default")
      (node (ref "C8") (pin "2") (pinfunction "2_2") (pintype "passive"))
      (node (ref "U2") (pin "22") (pinfunction "BST1_22") (pintype "passive"))
    )
    (net (code "55") (name "Net-(U2-BST2)") (class "Default")
      (node (ref "C9") (pin "2") (pinfunction "2_2") (pintype "passive"))
      (node (ref "U2") (pin "27") (pinfunction "BST2_27") (pintype "passive"))
    )
    (net (code "56") (name "Net-(U2-CSN1)") (class "Default")
      (node (ref "C10") (pin "2") (pinfunction "2_2") (pintype "passive"))
      (node (ref "R8") (pin "2") (pinfunction "2_2") (pintype "passive"))
      (node (ref "U2") (pin "19") (pinfunction "CSN1_19") (pintype "passive"))
    )
    (net (code "57") (name "Net-(U2-CSN2)") (class "Default")
      (node (ref "C7") (pin "1") (pinfunction "1_1") (pintype "passive"))
      (node (ref "R9") (pin "2") (pinfunction "2_2") (pintype "passive"))
      (node (ref "U2") (pin "30") (pinfunction "CSN2_30") (pintype "passive"))
    )
    (net (code "58") (name "Net-(U2-IGND)") (class "Default")
      (node (ref "RNC") (pin "2") (pinfunction "2_2") (pintype "passive"))
      (node (ref "U2") (pin "42") (pinfunction "IGND_42") (pintype "passive"))
    )
    (net (code "59") (name "Net-(U2-ISENCE)") (class "Default")
      (node (ref "RNC") (pin "1") (pinfunction "1_1") (pintype "passive"))
      (node (ref "U2") (pin "43") (pinfunction "ISENCE_43") (pintype "passive"))
    )
    (net (code "60") (name "Net-(U2-LX1)") (class "Default")
      (node (ref "C8") (pin "1") (pinfunction "1_1") (pintype "passive"))
      (node (ref "L1") (pin "1") (pinfunction "1_1") (pintype "passive"))
      (node (ref "Q3") (pin "1") (pinfunction "S_1") (pintype "passive"))
      (node (ref "Q3") (pin "2") (pinfunction "S_2") (pintype "passive"))
      (node (ref "Q3") (pin "3") (pinfunction "S_3") (pintype "passive"))
      (node (ref "Q5") (pin "5") (pinfunction "D_5") (pintype "passive"))
      (node (ref "Q5") (pin "6") (pinfunction "D_6") (pintype "passive"))
      (node (ref "Q5") (pin "7") (pinfunction "D_7") (pintype "passive"))
      (node (ref "Q5") (pin "8") (pinfunction "D_8") (pintype "passive"))
      (node (ref "R12") (pin "2") (pinfunction "2_2") (pintype "passive"))
      (node (ref "U2") (pin "23") (pinfunction "LX1_23") (pintype "passive"))
    )
    (net (code "61") (name "Net-(U2-LX2)") (class "Default")
      (node (ref "C9") (pin "1") (pinfunction "1_1") (pintype "passive"))
      (node (ref "L1") (pin "2") (pinfunction "2_2") (pintype "passive"))
      (node (ref "Q4") (pin "1") (pinfunction "S_1") (pintype "passive"))
      (node (ref "Q4") (pin "2") (pinfunction "S_2") (pintype "passive"))
      (node (ref "Q4") (pin "3") (pinfunction "S_3") (pintype "passive"))
      (node (ref "Q6") (pin "5") (pinfunction "D_5") (pintype "passive"))
      (node (ref "Q6") (pin "6") (pinfunction "D_6") (pintype "passive"))
      (node (ref "Q6") (pin "7") (pinfunction "D_7") (pintype "passive"))
      (node (ref "Q6") (pin "8") (pinfunction "D_8") (pintype "passive"))
      (node (ref "R13") (pin "2") (pinfunction "2_2") (pintype "passive"))
      (node (ref "U2") (pin "26") (pinfunction "LX2_26") (pintype "passive"))
    )
    (net (code "62") (name "Net-(U2-PCIN)") (class "Default")
      (node (ref "Q3") (pin "5") (pinfunction "D_5") (pintype "passive"))
      (node (ref "Q3") (pin "6") (pinfunction "D_6") (pintype "passive"))
      (node (ref "Q3") (pin "7") (pinfunction "D_7") (pintype "passive"))
      (node (ref "Q3") (pin "8") (pinfunction "D_8") (pintype "passive"))
      (node (ref "R10") (pin "2") (pinfunction "2_2") (pintype "passive"))
      (node (ref "R8") (pin "1") (pinfunction "1_1") (pintype "passive"))
      (node (ref "U2") (pin "20") (pinfunction "PCIN_20") (pintype "passive"))
    )
    (net (code "63") (name "Net-(U2-PCON)") (class "Default")
      (node (ref "Q4") (pin "5") (pinfunction "D_5") (pintype "passive"))
      (node (ref "Q4") (pin "6") (pinfunction "D_6") (pintype "passive"))
      (node (ref "Q4") (pin "7") (pinfunction "D_7") (pintype "passive"))
      (node (ref "Q4") (pin "8") (pinfunction "D_8") (pintype "passive"))
      (node (ref "R11") (pin "1") (pinfunction "1_1") (pintype "passive"))
      (node (ref "R9") (pin "1") (pinfunction "1_1") (pintype "passive"))
      (node (ref "U2") (pin "29") (pinfunction "PCON_29") (pintype "passive"))
    )
    (net (code "64") (name "Net-(U2-VCC5V)") (class "Default")
      (node (ref "C4") (pin "1") (pinfunction "1_1") (pintype "passive"))
      (node (ref "U2") (pin "34") (pinfunction "VCC5V_34") (pintype "passive"))
    )
    (net (code "65") (name "unconnected-(J2-SBU1-PadA8)") (class "Default")
      (node (ref "J2") (pin "A8") (pinfunction "SBU1_A8") (pintype "passive+no_connect"))
    )
    (net (code "66") (name "unconnected-(J2-SBU2-PadB8)") (class "Default")
      (node (ref "J2") (pin "B8") (pinfunction "SBU2_B8") (pintype "passive+no_connect"))
    )
    (net (code "67") (name "unconnected-(U2-CC3-Pad2)") (class "Default")
      (node (ref "U2") (pin "2") (pinfunction "CC3_2") (pintype "passive+no_connect"))
    )
    (net (code "68") (name "unconnected-(U2-CC4-Pad5)") (class "Default")
      (node (ref "U2") (pin "5") (pinfunction "CC4_5") (pintype "passive+no_connect"))
    )
    (net (code "69") (name "unconnected-(U2-DMB-Pad4)") (class "Default")
      (node (ref "U2") (pin "4") (pinfunction "DMB_4") (pintype "passive+no_connect"))
    )
    (net (code "70") (name "unconnected-(U2-DPB-Pad3)") (class "Default")
      (node (ref "U2") (pin "3") (pinfunction "DPB_3") (pintype "passive+no_connect"))
    )
    (net (code "71") (name "unconnected-(U2-LT-Pad1)") (class "Default")
      (node (ref "U2") (pin "1") (pinfunction "LT_1") (pintype "passive+no_connect"))
    )
    (net (code "72") (name "unconnected-(U2-LX-Pad33)") (class "Default")
      (node (ref "U2") (pin "33") (pinfunction "LX_33") (pintype "passive+no_connect"))
    )
    (net (code "73") (name "unconnected-(U2-VIN-Pad10)") (class "Default")
      (node (ref "U2") (pin "10") (pinfunction "VIN_10") (pintype "passive+no_connect"))
    )
    (net (code "74") (name "unconnected-(U2-VING-Pad11)") (class "Default")
      (node (ref "U2") (pin "11") (pinfunction "VING_11") (pintype "passive+no_connect"))
    )
    (net (code "75") (name "unconnected-(U2-VIN_I-Pad12)") (class "Default")
      (node (ref "U2") (pin "12") (pinfunction "VIN_I_12") (pintype "passive+no_connect"))
    )
  )
)
